# 0084_-_MCU.net
KiCad netlist of a schematic drawn in Altium Designer
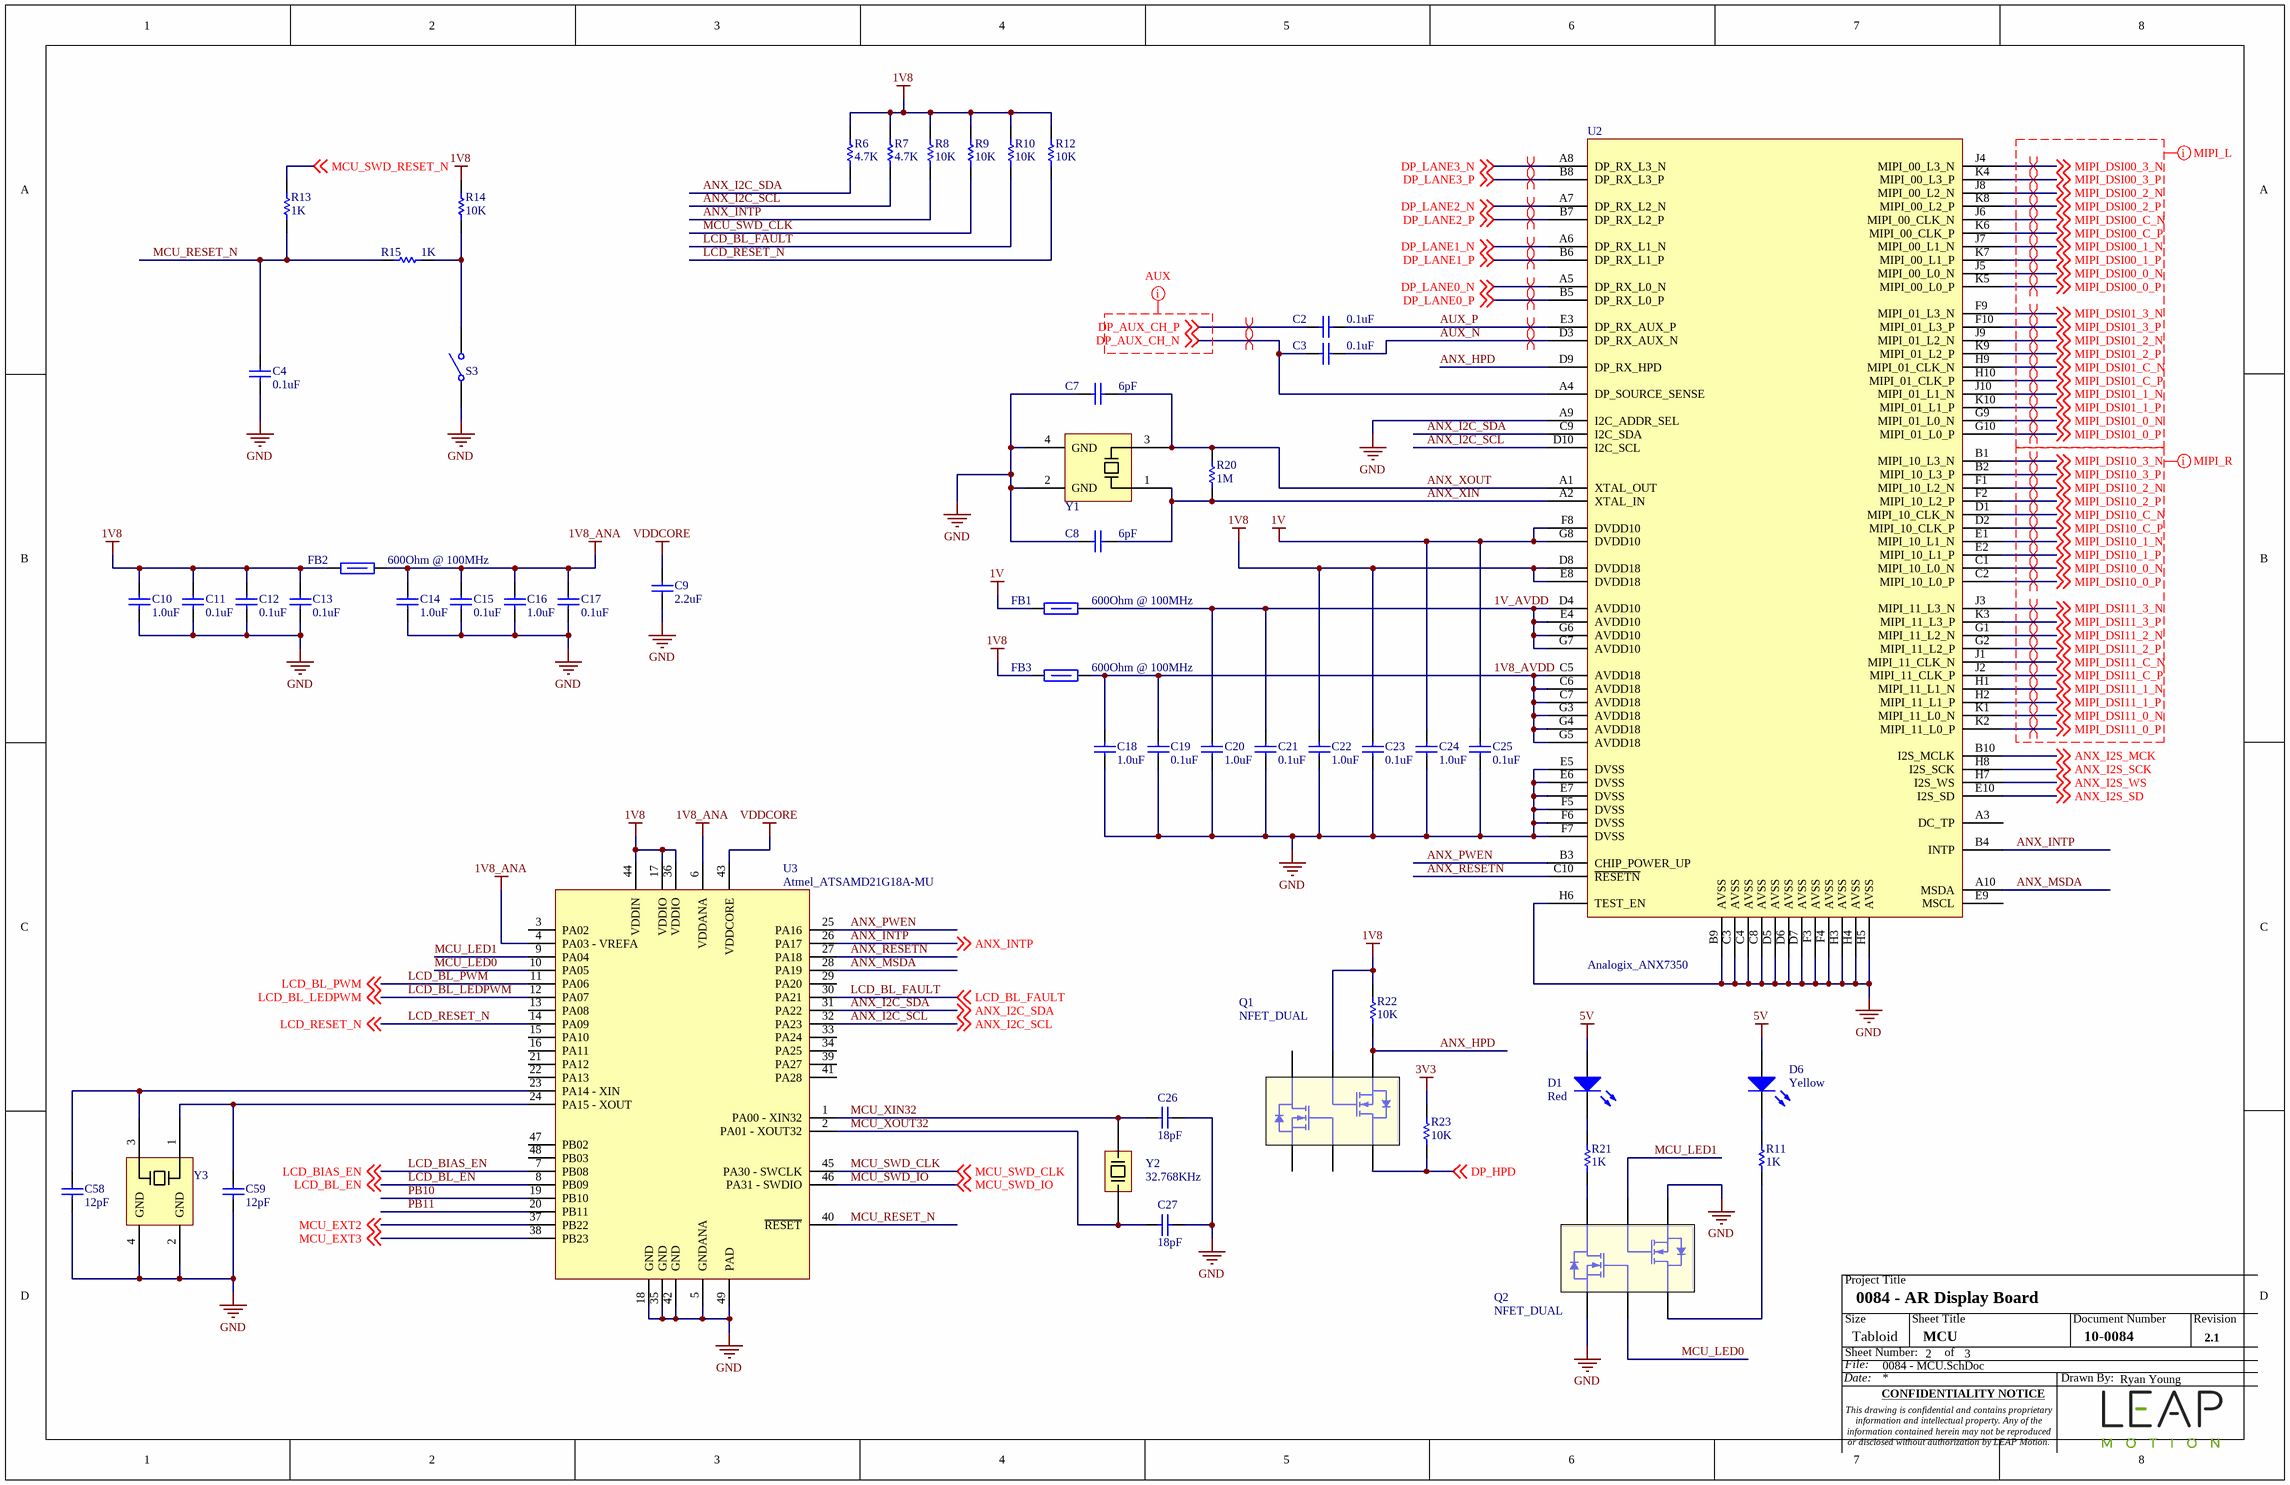
[diagram p0: 0084 - MCU.SchDoc]

(export (version "E")
  (design (tool "Eeschema 10.0.6"))
  (components
    (comp (ref "C2")
      (value "0.1uF")
      (footprint "CAPC0201(0603)33_N")
      (description "Capacitor, 0.1uF, 10V, 10%, 0201, Ceramic, X5R")
      (fields
        (field (name "MANUFACTURER") "Murata")
        (field (name "TOLERANCE") "10%")
        (field (name "AUTHOR") "AA")
      )
      (libsource (lib "LEAPdb") (part "CAP"))
    )
    (comp (ref "C3")
      (value "0.1uF")
      (footprint "CAPC0201(0603)33_N")
      (description "Capacitor, 0.1uF, 10V, 10%, 0201, Ceramic, X5R")
      (fields
        (field (name "MANUFACTURER") "Murata")
        (field (name "TOLERANCE") "10%")
        (field (name "AUTHOR") "AA")
      )
      (libsource (lib "LEAPdb") (part "CAP"))
    )
    (comp (ref "C4")
      (value "0.1uF")
      (footprint "CAPC0201(0603)33_N")
      (description "Capacitor, 0.1uF, 10V, 10%, 0201, Ceramic, X5R")
      (fields
        (field (name "MANUFACTURER") "Murata")
        (field (name "TOLERANCE") "10%")
        (field (name "AUTHOR") "AA")
      )
      (libsource (lib "LEAPdb") (part "CAP"))
    )
    (comp (ref "C7")
      (value "6pF")
      (footprint "CAPC0201(0603)33_N")
      (description "Capacitor, 6pF, 50V, 0.1pF, 0201, Ceramic, C0G(NP0)")
      (fields
        (field (name "MANUFACTURER") "Murata")
        (field (name "TOLERANCE") "0.1pF")
        (field (name "AUTHOR") "RY")
      )
      (libsource (lib "LEAPdb") (part "CAP"))
    )
    (comp (ref "C8")
      (value "6pF")
      (footprint "CAPC0201(0603)33_N")
      (description "Capacitor, 6pF, 50V, 0.1pF, 0201, Ceramic, C0G(NP0)")
      (fields
        (field (name "MANUFACTURER") "Murata")
        (field (name "TOLERANCE") "0.1pF")
        (field (name "AUTHOR") "RY")
      )
      (libsource (lib "LEAPdb") (part "CAP"))
    )
    (comp (ref "C9")
      (value "2.2uF")
      (footprint "CAPC0402(1005)60_N")
      (description "Capacitor, 2.2uF, 6.3V, 20%, 0402, Ceramic, X5R")
      (fields
        (field (name "MANUFACTURER") "TDK")
        (field (name "TOLERANCE") "20%")
        (field (name "AUTHOR") "NR")
      )
      (libsource (lib "LEAPdb") (part "CAP"))
    )
    (comp (ref "C10")
      (value "1.0uF")
      (footprint "CAPC0402(1005)60_N")
      (description "Capacitor, 1.0uF, 10V, 10%, 0402, Ceramic, X5R")
      (fields
        (field (name "MANUFACTURER") "TDK")
        (field (name "TOLERANCE") "10%")
        (field (name "AUTHOR") "NR")
      )
      (libsource (lib "LEAPdb") (part "CAP"))
    )
    (comp (ref "C11")
      (value "0.1uF")
      (footprint "CAPC0201(0603)33_N")
      (description "Capacitor, 0.1uF, 10V, 10%, 0201, Ceramic, X5R")
      (fields
        (field (name "MANUFACTURER") "Murata")
        (field (name "TOLERANCE") "10%")
        (field (name "AUTHOR") "AA")
      )
      (libsource (lib "LEAPdb") (part "CAP"))
    )
    (comp (ref "C12")
      (value "0.1uF")
      (footprint "CAPC0201(0603)33_N")
      (description "Capacitor, 0.1uF, 10V, 10%, 0201, Ceramic, X5R")
      (fields
        (field (name "MANUFACTURER") "Murata")
        (field (name "TOLERANCE") "10%")
        (field (name "AUTHOR") "AA")
      )
      (libsource (lib "LEAPdb") (part "CAP"))
    )
    (comp (ref "C13")
      (value "0.1uF")
      (footprint "CAPC0201(0603)33_N")
      (description "Capacitor, 0.1uF, 10V, 10%, 0201, Ceramic, X5R")
      (fields
        (field (name "MANUFACTURER") "Murata")
        (field (name "TOLERANCE") "10%")
        (field (name "AUTHOR") "AA")
      )
      (libsource (lib "LEAPdb") (part "CAP"))
    )
    (comp (ref "C14")
      (value "1.0uF")
      (footprint "CAPC0402(1005)60_N")
      (description "Capacitor, 1.0uF, 10V, 10%, 0402, Ceramic, X5R")
      (fields
        (field (name "MANUFACTURER") "TDK")
        (field (name "TOLERANCE") "10%")
        (field (name "AUTHOR") "NR")
      )
      (libsource (lib "LEAPdb") (part "CAP"))
    )
    (comp (ref "C15")
      (value "0.1uF")
      (footprint "CAPC0201(0603)33_N")
      (description "Capacitor, 0.1uF, 10V, 10%, 0201, Ceramic, X5R")
      (fields
        (field (name "MANUFACTURER") "Murata")
        (field (name "TOLERANCE") "10%")
        (field (name "AUTHOR") "AA")
      )
      (libsource (lib "LEAPdb") (part "CAP"))
    )
    (comp (ref "C16")
      (value "1.0uF")
      (footprint "CAPC0402(1005)60_N")
      (description "Capacitor, 1.0uF, 10V, 10%, 0402, Ceramic, X5R")
      (fields
        (field (name "MANUFACTURER") "TDK")
        (field (name "TOLERANCE") "10%")
        (field (name "AUTHOR") "NR")
      )
      (libsource (lib "LEAPdb") (part "CAP"))
    )
    (comp (ref "C17")
      (value "0.1uF")
      (footprint "CAPC0201(0603)33_N")
      (description "Capacitor, 0.1uF, 10V, 10%, 0201, Ceramic, X5R")
      (fields
        (field (name "MANUFACTURER") "Murata")
        (field (name "TOLERANCE") "10%")
        (field (name "AUTHOR") "AA")
      )
      (libsource (lib "LEAPdb") (part "CAP"))
    )
    (comp (ref "C18")
      (value "1.0uF")
      (footprint "CAPC0402(1005)60_L")
      (description "Capacitor, 1.0uF, 10V, 10%, 0402, Ceramic, X5R")
      (fields
        (field (name "MANUFACTURER") "TDK")
        (field (name "TOLERANCE") "10%")
        (field (name "AUTHOR") "NR")
      )
      (libsource (lib "LEAPdb") (part "CAP"))
    )
    (comp (ref "C19")
      (value "0.1uF")
      (footprint "CAPC0201(0603)33_L")
      (description "Capacitor, 0.1uF, 10V, 10%, 0201, Ceramic, X5R")
      (fields
        (field (name "MANUFACTURER") "Murata")
        (field (name "TOLERANCE") "10%")
        (field (name "AUTHOR") "AA")
      )
      (libsource (lib "LEAPdb") (part "CAP"))
    )
    (comp (ref "C20")
      (value "1.0uF")
      (footprint "CAPC0402(1005)60_L")
      (description "Capacitor, 1.0uF, 10V, 10%, 0402, Ceramic, X5R")
      (fields
        (field (name "MANUFACTURER") "TDK")
        (field (name "TOLERANCE") "10%")
        (field (name "AUTHOR") "NR")
      )
      (libsource (lib "LEAPdb") (part "CAP"))
    )
    (comp (ref "C21")
      (value "0.1uF")
      (footprint "CAPC0201(0603)33_L")
      (description "Capacitor, 0.1uF, 10V, 10%, 0201, Ceramic, X5R")
      (fields
        (field (name "MANUFACTURER") "Murata")
        (field (name "TOLERANCE") "10%")
        (field (name "AUTHOR") "AA")
      )
      (libsource (lib "LEAPdb") (part "CAP"))
    )
    (comp (ref "C22")
      (value "1.0uF")
      (footprint "CAPC0402(1005)60_L")
      (description "Capacitor, 1.0uF, 10V, 10%, 0402, Ceramic, X5R")
      (fields
        (field (name "MANUFACTURER") "TDK")
        (field (name "TOLERANCE") "10%")
        (field (name "AUTHOR") "NR")
      )
      (libsource (lib "LEAPdb") (part "CAP"))
    )
    (comp (ref "C23")
      (value "0.1uF")
      (footprint "CAPC0201(0603)33_L")
      (description "Capacitor, 0.1uF, 10V, 10%, 0201, Ceramic, X5R")
      (fields
        (field (name "MANUFACTURER") "Murata")
        (field (name "TOLERANCE") "10%")
        (field (name "AUTHOR") "AA")
      )
      (libsource (lib "LEAPdb") (part "CAP"))
    )
    (comp (ref "C24")
      (value "1.0uF")
      (footprint "CAPC0402(1005)60_L")
      (description "Capacitor, 1.0uF, 10V, 10%, 0402, Ceramic, X5R")
      (fields
        (field (name "MANUFACTURER") "TDK")
        (field (name "TOLERANCE") "10%")
        (field (name "AUTHOR") "NR")
      )
      (libsource (lib "LEAPdb") (part "CAP"))
    )
    (comp (ref "C25")
      (value "0.1uF")
      (footprint "CAPC0201(0603)33_L")
      (description "Capacitor, 0.1uF, 10V, 10%, 0201, Ceramic, X5R")
      (fields
        (field (name "MANUFACTURER") "Murata")
        (field (name "TOLERANCE") "10%")
        (field (name "AUTHOR") "AA")
      )
      (libsource (lib "LEAPdb") (part "CAP"))
    )
    (comp (ref "C26")
      (value "18pF")
      (footprint "CAPC0201(0603)33_N")
      (description "Capacitor, 18pF, 50V, 2%, 0201, Ceramic, C0G(NP0)")
      (fields
        (field (name "MANUFACTURER") "Murata")
        (field (name "TOLERANCE") "2%")
        (field (name "AUTHOR") "RY")
      )
      (libsource (lib "LEAPdb") (part "CAP"))
    )
    (comp (ref "C27")
      (value "18pF")
      (footprint "CAPC0201(0603)33_N")
      (description "Capacitor, 18pF, 50V, 2%, 0201, Ceramic, C0G(NP0)")
      (fields
        (field (name "MANUFACTURER") "Murata")
        (field (name "TOLERANCE") "2%")
        (field (name "AUTHOR") "RY")
      )
      (libsource (lib "LEAPdb") (part "CAP"))
    )
    (comp (ref "C58")
      (value "12pF")
      (footprint "CAPC0201(0603)33_N")
      (description "Capacitor, 12pF, 50V, 2%, 0201, Ceramic, C0G(NP0)")
      (fields
        (field (name "MANUFACTURER") "Murata")
        (field (name "TOLERANCE") "2%")
        (field (name "AUTHOR") "RY")
      )
      (libsource (lib "LEAPdb") (part "CAP"))
    )
    (comp (ref "C59")
      (value "12pF")
      (footprint "CAPC0201(0603)33_N")
      (description "Capacitor, 12pF, 50V, 2%, 0201, Ceramic, C0G(NP0)")
      (fields
        (field (name "MANUFACTURER") "Murata")
        (field (name "TOLERANCE") "2%")
        (field (name "AUTHOR") "RY")
      )
      (libsource (lib "LEAPdb") (part "CAP"))
    )
    (comp (ref "D1")
      (value "~")
      (footprint "Dialight_598-8010-107F")
      (description "LED, 635nm, 140deg, , 20mA, , 1.6mm x 0.8mm, -30C - 85C")
      (fields
        (field (name "MANUFACTURER") "Dialight")
        (field (name "COLOR") "Red")
        (field (name "AUTHOR") "JDS")
      )
      (libsource (lib "LEAPdb") (part "LED"))
    )
    (comp (ref "D6")
      (value "~")
      (footprint "Dialight_598-8040-107F")
      (description "LED, 593nm, 140deg, , 20mA, , 1.6mm x 0.8mm, -30C - 85C")
      (fields
        (field (name "MANUFACTURER") "Dialight")
        (field (name "COLOR") "Yellow")
        (field (name "AUTHOR") "JDS")
      )
      (libsource (lib "LEAPdb") (part "LED"))
    )
    (comp (ref "FB1")
      (value "Ferrite Bead")
      (footprint "INDC1608X09N")
      (description "FERRITE CHIP BEAD 600 OHM SMD")
      (fields
        (field (name "MANUFACTURER") "TDK")
        (field (name "IMPEDANCE @ FREQ") "600Ohm @ 100MHz")
        (field (name "AUTHOR") "NR")
      )
      (libsource (lib "LEAPdb") (part "Ferrite Bead"))
    )
    (comp (ref "FB2")
      (value "Ferrite Bead")
      (footprint "INDC1608X09N")
      (description "FERRITE CHIP BEAD 600 OHM SMD")
      (fields
        (field (name "MANUFACTURER") "TDK")
        (field (name "IMPEDANCE @ FREQ") "600Ohm @ 100MHz")
        (field (name "AUTHOR") "NR")
      )
      (libsource (lib "LEAPdb") (part "Ferrite Bead"))
    )
    (comp (ref "FB3")
      (value "Ferrite Bead")
      (footprint "INDC1608X09N")
      (description "FERRITE CHIP BEAD 600 OHM SMD")
      (fields
        (field (name "MANUFACTURER") "TDK")
        (field (name "IMPEDANCE @ FREQ") "600Ohm @ 100MHz")
        (field (name "AUTHOR") "NR")
      )
      (libsource (lib "LEAPdb") (part "Ferrite Bead"))
    )
    (comp (ref "Q1")
      (value "NFET_DUAL")
      (footprint "SOT-563")
      (description "Transistor, NFET_DUAL, 2.2Ohm, 200mA, 120mW, 	SOT-563, -55C - 150C")
      (fields (field (name "MANUFACTURER") "Rohm Semiconductor") (field (name "AUTHOR") "RY"))
      (libsource (lib "LEAPdb") (part "NFET_DUAL"))
    )
    (comp (ref "Q2")
      (value "NFET_DUAL")
      (footprint "SOT-563")
      (description "Transistor, NFET_DUAL, 2.2Ohm, 200mA, 120mW, 	SOT-563, -55C - 150C")
      (fields (field (name "MANUFACTURER") "Rohm Semiconductor") (field (name "AUTHOR") "RY"))
      (libsource (lib "LEAPdb") (part "NFET_DUAL"))
    )
    (comp (ref "R6")
      (value "4.7K")
      (footprint "RESC0201(0603)_N")
      (description "Resistor, 4.7K, 1/20W, 1%, 0201")
      (fields
        (field (name "MANUFACTURER") "Panasonic Electronic Components")
        (field (name "TOLERANCE") "1%")
        (field (name "AUTHOR") "NR")
      )
      (libsource (lib "LEAPdb") (part "RES"))
    )
    (comp (ref "R7")
      (value "4.7K")
      (footprint "RESC0201(0603)_N")
      (description "Resistor, 4.7K, 1/20W, 1%, 0201")
      (fields
        (field (name "MANUFACTURER") "Panasonic Electronic Components")
        (field (name "TOLERANCE") "1%")
        (field (name "AUTHOR") "NR")
      )
      (libsource (lib "LEAPdb") (part "RES"))
    )
    (comp (ref "R8")
      (value "10K")
      (footprint "RESC0201(0603)_N")
      (description "Resistor, 10K, 1/20W, 5%, 0201")
      (fields
        (field (name "MANUFACTURER") "Panasonic Electronic Components")
        (field (name "TOLERANCE") "5%")
        (field (name "AUTHOR") "NR")
      )
      (libsource (lib "LEAPdb") (part "RES"))
    )
    (comp (ref "R9")
      (value "10K")
      (footprint "RESC0201(0603)_N")
      (description "Resistor, 10K, 1/20W, 5%, 0201")
      (fields
        (field (name "MANUFACTURER") "Panasonic Electronic Components")
        (field (name "TOLERANCE") "5%")
        (field (name "AUTHOR") "NR")
      )
      (libsource (lib "LEAPdb") (part "RES"))
    )
    (comp (ref "R10")
      (value "10K")
      (footprint "RESC0201(0603)_N")
      (description "Resistor, 10K, 1/20W, 5%, 0201")
      (fields
        (field (name "MANUFACTURER") "Panasonic Electronic Components")
        (field (name "TOLERANCE") "5%")
        (field (name "AUTHOR") "NR")
      )
      (libsource (lib "LEAPdb") (part "RES"))
    )
    (comp (ref "R11")
      (value "1K")
      (footprint "RESC0201(0603)_N")
      (description "Resistor, 1K, 1/20W, 5%, 0201")
      (fields
        (field (name "MANUFACTURER") "Panasonic Electronic Components")
        (field (name "TOLERANCE") "5%")
        (field (name "AUTHOR") "JDS")
      )
      (libsource (lib "LEAPdb") (part "RES"))
    )
    (comp (ref "R12")
      (value "10K")
      (footprint "RESC0201(0603)_N")
      (description "Resistor, 10K, 1/20W, 5%, 0201")
      (fields
        (field (name "MANUFACTURER") "Panasonic Electronic Components")
        (field (name "TOLERANCE") "5%")
        (field (name "AUTHOR") "NR")
      )
      (libsource (lib "LEAPdb") (part "RES"))
    )
    (comp (ref "R13")
      (value "1K")
      (footprint "RESC0201(0603)_N")
      (description "Resistor, 1K, 1/20W, 5%, 0201")
      (fields
        (field (name "MANUFACTURER") "Panasonic Electronic Components")
        (field (name "TOLERANCE") "5%")
        (field (name "AUTHOR") "JDS")
      )
      (libsource (lib "LEAPdb") (part "RES"))
    )
    (comp (ref "R14")
      (value "10K")
      (footprint "RESC0201(0603)_N")
      (description "Resistor, 10K, 1/20W, 5%, 0201")
      (fields
        (field (name "MANUFACTURER") "Panasonic Electronic Components")
        (field (name "TOLERANCE") "5%")
        (field (name "AUTHOR") "NR")
      )
      (libsource (lib "LEAPdb") (part "RES"))
    )
    (comp (ref "R15")
      (value "1K")
      (footprint "RESC0201(0603)_N")
      (description "Resistor, 1K, 1/20W, 5%, 0201")
      (fields
        (field (name "MANUFACTURER") "Panasonic Electronic Components")
        (field (name "TOLERANCE") "5%")
        (field (name "AUTHOR") "JDS")
      )
      (libsource (lib "LEAPdb") (part "RES"))
    )
    (comp (ref "R20")
      (value "1M")
      (footprint "RESC0201(0603)_N")
      (description "Resistor, 1M, 1/20W, 1%, 0201")
      (fields
        (field (name "MANUFACTURER") "Panasonic Electronic Components")
        (field (name "TOLERANCE") "1%")
        (field (name "AUTHOR") "RY")
      )
      (libsource (lib "LEAPdb") (part "RES"))
    )
    (comp (ref "R21")
      (value "1K")
      (footprint "RESC0201(0603)_N")
      (description "Resistor, 1K, 1/20W, 5%, 0201")
      (fields
        (field (name "MANUFACTURER") "Panasonic Electronic Components")
        (field (name "TOLERANCE") "5%")
        (field (name "AUTHOR") "JDS")
      )
      (libsource (lib "LEAPdb") (part "RES"))
    )
    (comp (ref "R22")
      (value "10K")
      (footprint "RESC0201(0603)_N")
      (description "Resistor, 10K, 1/20W, 5%, 0201")
      (fields
        (field (name "MANUFACTURER") "Panasonic Electronic Components")
        (field (name "TOLERANCE") "5%")
        (field (name "AUTHOR") "NR")
      )
      (libsource (lib "LEAPdb") (part "RES"))
    )
    (comp (ref "R23")
      (value "10K")
      (footprint "RESC0201(0603)_N")
      (description "Resistor, 10K, 1/20W, 5%, 0201")
      (fields
        (field (name "MANUFACTURER") "Panasonic Electronic Components")
        (field (name "TOLERANCE") "5%")
        (field (name "AUTHOR") "NR")
      )
      (libsource (lib "LEAPdb") (part "RES"))
    )
    (comp (ref "S3")
      (value "SW-SPST")
      (footprint "ALPS_SKRPABE010")
      (description "Switch, SPST-NO, Button, 4.6mm x 3.2mm")
      (fields (field (name "MANUFACTURER") "ALPS") (field (name "AUTHOR") "JDS"))
      (libsource (lib "LEAPdb") (part "SW-SPST"))
    )
    (comp (ref "U2")
      (value "Analogix_ANX7350")
      (footprint "Analogix_ANX7350")
      (description "DisplayPort 1.4-to-Dual MIPI Output Converter")
      (fields (field (name "MANUFACTURER") "Analogix") (field (name "AUTHOR") "RY"))
      (libsource (lib "LEAPdb") (part "Analogix_ANX7350"))
    )
    (comp (ref "U3")
      (value "Atmel_ATSAMD21G18A-MU")
      (footprint "Atmel_ATSAMD21G18A-MU")
      (description "IC MCU 32BIT 256KB FLASH 48QFN")
      (fields (field (name "MANUFACTURER") "Atmel") (field (name "AUTHOR") "RY"))
      (libsource (lib "LEAPdb") (part "Atmel_ATSAMD21G18A-MU"))
    )
    (comp (ref "Y1")
      (value "Crystal")
      (footprint "Abracon_ABM11")
      (description "Crystal, 24MHz, 6pF, 4-SMD (2x1.6)")
      (fields
        (field (name "MANUFACTURER") "Abracon")
        (field (name "TOLERANCE") "20ppm")
        (field (name "AUTHOR") "AA")
      )
      (libsource (lib "LEAPdb") (part "Crystal"))
    )
    (comp (ref "Y2")
      (value "Crystal_2pin")
      (footprint "Abracon_ABS07")
      (description "Crystal, 32.768KHz, 12.5pF, 2-SMD(3.2x1.5)")
      (fields
        (field (name "MANUFACTURER") "Abracon")
        (field (name "FREQUENCY") "32.768KHz")
        (field (name "TOLERANCE") "20 ppm")
        (field (name "AUTHOR") "JDS")
      )
      (libsource (lib "LEAPdb") (part "Crystal_2pin"))
    )
    (comp (ref "Y3")
      (value "Crystal")
      (footprint "Abracon_ABM11")
      (description "Crystal, 16MHz, 10pF, 4-SMD (2x1.6)")
      (fields
        (field (name "MANUFACTURER") "Abracon")
        (field (name "TOLERANCE") "20ppm")
        (field (name "AUTHOR") "JDS")
      )
      (libsource (lib "") (part "Crystal_1"))
    )
  )
  (nets
    (net (code "1") (name "/1V8_AVDD") (class "Default")
      (node (ref "C18") (pin "2") (pinfunction "2_2") (pintype "passive"))
      (node (ref "C19") (pin "2") (pinfunction "2_2") (pintype "passive"))
      (node (ref "FB3") (pin "2") (pinfunction "2_2") (pintype "passive"))
      (node (ref "U2") (pin "C5") (pinfunction "AVDD18_C5") (pintype "passive"))
      (node (ref "U2") (pin "C6") (pinfunction "AVDD18_C6") (pintype "passive"))
      (node (ref "U2") (pin "C7") (pinfunction "AVDD18_C7") (pintype "passive"))
      (node (ref "U2") (pin "G3") (pinfunction "AVDD18_G3") (pintype "passive"))
      (node (ref "U2") (pin "G4") (pinfunction "AVDD18_G4") (pintype "passive"))
      (node (ref "U2") (pin "G5") (pinfunction "AVDD18_G5") (pintype "passive"))
    )
    (net (code "2") (name "/1V_AVDD") (class "Default")
      (node (ref "C20") (pin "2") (pinfunction "2_2") (pintype "passive"))
      (node (ref "C21") (pin "2") (pinfunction "2_2") (pintype "passive"))
      (node (ref "FB1") (pin "2") (pinfunction "2_2") (pintype "passive"))
      (node (ref "U2") (pin "D4") (pinfunction "AVDD10_D4") (pintype "passive"))
      (node (ref "U2") (pin "E4") (pinfunction "AVDD10_E4") (pintype "passive"))
      (node (ref "U2") (pin "G6") (pinfunction "AVDD10_G6") (pintype "passive"))
      (node (ref "U2") (pin "G7") (pinfunction "AVDD10_G7") (pintype "passive"))
    )
    (net (code "3") (name "/ANX_HPD") (class "Default")
      (node (ref "Q1") (pin "4") (pinfunction "S2_4") (pintype "passive"))
      (node (ref "R22") (pin "1") (pinfunction "1_1") (pintype "passive"))
      (node (ref "U2") (pin "D9") (pinfunction "DP_RX_HPD_D9") (pintype "passive"))
    )
    (net (code "4") (name "/ANX_MSDA") (class "Default")
      (node (ref "U2") (pin "A10") (pinfunction "MSDA_A10") (pintype "passive"))
      (node (ref "U3") (pin "28") (pinfunction "PA19_28") (pintype "passive"))
    )
    (net (code "5") (name "/ANX_PWEN") (class "Default")
      (node (ref "U2") (pin "B3") (pinfunction "CHIP_POWER_UP_B3") (pintype "passive"))
      (node (ref "U3") (pin "25") (pinfunction "PA16_25") (pintype "passive"))
    )
    (net (code "6") (name "/ANX_RESETN") (class "Default")
      (node (ref "U2") (pin "C10") (pinfunction "~{RESETN}_C10") (pintype "passive"))
      (node (ref "U3") (pin "27") (pinfunction "PA18_27") (pintype "passive"))
    )
    (net (code "7") (name "/ANX_XIN") (class "Default")
      (node (ref "C8") (pin "1") (pinfunction "1_1") (pintype "passive"))
      (node (ref "R20") (pin "1") (pinfunction "1_1") (pintype "passive"))
      (node (ref "U2") (pin "A2") (pinfunction "XTAL_IN_A2") (pintype "passive"))
      (node (ref "Y1") (pin "1") (pinfunction "XTAL1_1") (pintype "passive"))
    )
    (net (code "8") (name "/ANX_XOUT") (class "Default")
      (node (ref "C7") (pin "1") (pinfunction "1_1") (pintype "passive"))
      (node (ref "R20") (pin "2") (pinfunction "2_2") (pintype "passive"))
      (node (ref "U2") (pin "A1") (pinfunction "XTAL_OUT_A1") (pintype "passive"))
      (node (ref "Y1") (pin "3") (pinfunction "XTAL2_3") (pintype "passive"))
    )
    (net (code "9") (name "/AUX_N") (class "Default")
      (node (ref "C3") (pin "1") (pinfunction "1_1") (pintype "passive"))
      (node (ref "U2") (pin "D3") (pinfunction "DP_RX_AUX_N_D3") (pintype "passive"))
    )
    (net (code "10") (name "/AUX_P") (class "Default")
      (node (ref "C2") (pin "1") (pinfunction "1_1") (pintype "passive"))
      (node (ref "U2") (pin "E3") (pinfunction "DP_RX_AUX_P_E3") (pintype "passive"))
    )
    (net (code "11") (name "/MCU_LED0") (class "Default")
      (node (ref "Q2") (pin "2") (pinfunction "G1_2") (pintype "passive"))
      (node (ref "U3") (pin "10") (pinfunction "PA05_10") (pintype "passive"))
    )
    (net (code "12") (name "/MCU_LED1") (class "Default")
      (node (ref "Q2") (pin "5") (pinfunction "G2_5") (pintype "passive"))
      (node (ref "U3") (pin "9") (pinfunction "PA04_9") (pintype "passive"))
    )
    (net (code "13") (name "/MCU_RESET_N") (class "Default")
      (node (ref "C4") (pin "2") (pinfunction "2_2") (pintype "passive"))
      (node (ref "R13") (pin "2") (pinfunction "2_2") (pintype "passive"))
      (node (ref "R15") (pin "2") (pinfunction "2_2") (pintype "passive"))
      (node (ref "U3") (pin "40") (pinfunction "~{RESET}_40") (pintype "passive"))
    )
    (net (code "14") (name "/MCU_XIN32") (class "Default")
      (node (ref "C26") (pin "1") (pinfunction "1_1") (pintype "passive"))
      (node (ref "U3") (pin "1") (pinfunction "PA00_-_XIN32_1") (pintype "passive"))
      (node (ref "Y2") (pin "1") (pinfunction "XTAL2_1") (pintype "passive"))
    )
    (net (code "15") (name "/MCU_XOUT32") (class "Default")
      (node (ref "C27") (pin "1") (pinfunction "1_1") (pintype "passive"))
      (node (ref "U3") (pin "2") (pinfunction "PA01_-_XOUT32_2") (pintype "passive"))
      (node (ref "Y2") (pin "0") (pinfunction "XTAL1_0") (pintype "passive"))
    )
    (net (code "16") (name "/PB10") (class "Default")
      (node (ref "U3") (pin "19") (pinfunction "PB10_19") (pintype "passive"))
    )
    (net (code "17") (name "/PB11") (class "Default")
      (node (ref "U3") (pin "20") (pinfunction "PB11_20") (pintype "passive"))
    )
    (net (code "18") (name "1V") (class "Default")
      (node (ref "C24") (pin "2") (pinfunction "2_2") (pintype "passive"))
      (node (ref "C25") (pin "2") (pinfunction "2_2") (pintype "passive"))
      (node (ref "FB1") (pin "1") (pinfunction "1_1") (pintype "passive"))
      (node (ref "U2") (pin "F8") (pinfunction "DVDD10_F8") (pintype "passive"))
      (node (ref "U2") (pin "G8") (pinfunction "DVDD10_G8") (pintype "passive"))
    )
    (net (code "19") (name "1V8") (class "Default")
      (node (ref "C10") (pin "2") (pinfunction "2_2") (pintype "passive"))
      (node (ref "C11") (pin "2") (pinfunction "2_2") (pintype "passive"))
      (node (ref "C12") (pin "2") (pinfunction "2_2") (pintype "passive"))
      (node (ref "C13") (pin "2") (pinfunction "2_2") (pintype "passive"))
      (node (ref "C22") (pin "2") (pinfunction "2_2") (pintype "passive"))
      (node (ref "C23") (pin "2") (pinfunction "2_2") (pintype "passive"))
      (node (ref "FB2") (pin "1") (pinfunction "1_1") (pintype "passive"))
      (node (ref "FB3") (pin "1") (pinfunction "1_1") (pintype "passive"))
      (node (ref "Q1") (pin "5") (pinfunction "G2_5") (pintype "passive"))
      (node (ref "R10") (pin "2") (pinfunction "2_2") (pintype "passive"))
      (node (ref "R12") (pin "2") (pinfunction "2_2") (pintype "passive"))
      (node (ref "R14") (pin "2") (pinfunction "2_2") (pintype "passive"))
      (node (ref "R22") (pin "2") (pinfunction "2_2") (pintype "passive"))
      (node (ref "R6") (pin "2") (pinfunction "2_2") (pintype "passive"))
      (node (ref "R7") (pin "2") (pinfunction "2_2") (pintype "passive"))
      (node (ref "R8") (pin "2") (pinfunction "2_2") (pintype "passive"))
      (node (ref "R9") (pin "2") (pinfunction "2_2") (pintype "passive"))
      (node (ref "U2") (pin "D8") (pinfunction "DVDD18_D8") (pintype "passive"))
      (node (ref "U2") (pin "E8") (pinfunction "DVDD18_E8") (pintype "passive"))
      (node (ref "U3") (pin "17") (pinfunction "VDDIO_17") (pintype "passive"))
      (node (ref "U3") (pin "36") (pinfunction "VDDIO_36") (pintype "passive"))
      (node (ref "U3") (pin "44") (pinfunction "VDDIN_44") (pintype "passive"))
    )
    (net (code "20") (name "1V8_ANA") (class "Default")
      (node (ref "C14") (pin "2") (pinfunction "2_2") (pintype "passive"))
      (node (ref "C15") (pin "2") (pinfunction "2_2") (pintype "passive"))
      (node (ref "C16") (pin "2") (pinfunction "2_2") (pintype "passive"))
      (node (ref "C17") (pin "2") (pinfunction "2_2") (pintype "passive"))
      (node (ref "FB2") (pin "2") (pinfunction "2_2") (pintype "passive"))
      (node (ref "U3") (pin "4") (pinfunction "PA03_-_VREFA_4") (pintype "passive"))
      (node (ref "U3") (pin "6") (pinfunction "VDDANA_6") (pintype "passive"))
    )
    (net (code "21") (name "3V3") (class "Default")
      (node (ref "R23") (pin "1") (pinfunction "1_1") (pintype "passive"))
    )
    (net (code "22") (name "5V") (class "Default")
      (node (ref "D1") (pin "A") (pinfunction "A_A") (pintype "passive"))
      (node (ref "D6") (pin "A") (pinfunction "A_A") (pintype "passive"))
    )
    (net (code "23") (name "ANX_I2C_SCL") (class "Default")
      (node (ref "R7") (pin "1") (pinfunction "1_1") (pintype "passive"))
      (node (ref "U2") (pin "D10") (pinfunction "I2C_SCL_D10") (pintype "passive"))
      (node (ref "U3") (pin "32") (pinfunction "PA23_32") (pintype "passive"))
    )
    (net (code "24") (name "ANX_I2C_SDA") (class "Default")
      (node (ref "R6") (pin "1") (pinfunction "1_1") (pintype "passive"))
      (node (ref "U2") (pin "C9") (pinfunction "I2C_SDA_C9") (pintype "passive"))
      (node (ref "U3") (pin "31") (pinfunction "PA22_31") (pintype "passive"))
    )
    (net (code "25") (name "ANX_I2S_MCK") (class "Default")
      (node (ref "U2") (pin "B10") (pinfunction "I2S_MCLK_B10") (pintype "passive"))
    )
    (net (code "26") (name "ANX_I2S_SCK") (class "Default")
      (node (ref "U2") (pin "H8") (pinfunction "I2S_SCK_H8") (pintype "passive"))
    )
    (net (code "27") (name "ANX_I2S_SD") (class "Default")
      (node (ref "U2") (pin "E10") (pinfunction "I2S_SD_E10") (pintype "passive"))
    )
    (net (code "28") (name "ANX_I2S_WS") (class "Default")
      (node (ref "U2") (pin "H7") (pinfunction "I2S_WS_H7") (pintype "passive"))
    )
    (net (code "29") (name "ANX_INTP") (class "Default")
      (node (ref "R8") (pin "1") (pinfunction "1_1") (pintype "passive"))
      (node (ref "U2") (pin "B4") (pinfunction "INTP_B4") (pintype "passive"))
      (node (ref "U3") (pin "26") (pinfunction "PA17_26") (pintype "passive"))
    )
    (net (code "30") (name "DP_AUX_CH_N") (class "Default")
      (node (ref "C3") (pin "2") (pinfunction "2_2") (pintype "passive"))
      (node (ref "U2") (pin "A4") (pinfunction "DP_SOURCE_SENSE_A4") (pintype "passive"))
    )
    (net (code "31") (name "DP_AUX_CH_P") (class "Default")
      (node (ref "C2") (pin "2") (pinfunction "2_2") (pintype "passive"))
    )
    (net (code "32") (name "DP_HPD") (class "Default")
      (node (ref "Q1") (pin "3") (pinfunction "D2_3") (pintype "passive"))
      (node (ref "R23") (pin "2") (pinfunction "2_2") (pintype "passive"))
    )
    (net (code "33") (name "DP_LANE0_N") (class "Default")
      (node (ref "U2") (pin "A5") (pinfunction "DP_RX_L0_N_A5") (pintype "passive"))
    )
    (net (code "34") (name "DP_LANE0_P") (class "Default")
      (node (ref "U2") (pin "B5") (pinfunction "DP_RX_L0_P_B5") (pintype "passive"))
    )
    (net (code "35") (name "DP_LANE1_N") (class "Default")
      (node (ref "U2") (pin "A6") (pinfunction "DP_RX_L1_N_A6") (pintype "passive"))
    )
    (net (code "36") (name "DP_LANE1_P") (class "Default")
      (node (ref "U2") (pin "B6") (pinfunction "DP_RX_L1_P_B6") (pintype "passive"))
    )
    (net (code "37") (name "DP_LANE2_N") (class "Default")
      (node (ref "U2") (pin "A7") (pinfunction "DP_RX_L2_N_A7") (pintype "passive"))
    )
    (net (code "38") (name "DP_LANE2_P") (class "Default")
      (node (ref "U2") (pin "B7") (pinfunction "DP_RX_L2_P_B7") (pintype "passive"))
    )
    (net (code "39") (name "DP_LANE3_N") (class "Default")
      (node (ref "U2") (pin "A8") (pinfunction "DP_RX_L3_N_A8") (pintype "passive"))
    )
    (net (code "40") (name "DP_LANE3_P") (class "Default")
      (node (ref "U2") (pin "B8") (pinfunction "DP_RX_L3_P_B8") (pintype "passive"))
    )
    (net (code "41") (name "GND") (class "Default")
      (node (ref "C10") (pin "1") (pinfunction "1_1") (pintype "passive"))
      (node (ref "C11") (pin "1") (pinfunction "1_1") (pintype "passive"))
      (node (ref "C12") (pin "1") (pinfunction "1_1") (pintype "passive"))
      (node (ref "C13") (pin "1") (pinfunction "1_1") (pintype "passive"))
      (node (ref "C14") (pin "1") (pinfunction "1_1") (pintype "passive"))
      (node (ref "C15") (pin "1") (pinfunction "1_1") (pintype "passive"))
      (node (ref "C16") (pin "1") (pinfunction "1_1") (pintype "passive"))
      (node (ref "C17") (pin "1") (pinfunction "1_1") (pintype "passive"))
      (node (ref "C18") (pin "1") (pinfunction "1_1") (pintype "passive"))
      (node (ref "C19") (pin "1") (pinfunction "1_1") (pintype "passive"))
      (node (ref "C20") (pin "1") (pinfunction "1_1") (pintype "passive"))
      (node (ref "C21") (pin "1") (pinfunction "1_1") (pintype "passive"))
      (node (ref "C22") (pin "1") (pinfunction "1_1") (pintype "passive"))
      (node (ref "C23") (pin "1") (pinfunction "1_1") (pintype "passive"))
      (node (ref "C24") (pin "1") (pinfunction "1_1") (pintype "passive"))
      (node (ref "C25") (pin "1") (pinfunction "1_1") (pintype "passive"))
      (node (ref "C26") (pin "2") (pinfunction "2_2") (pintype "passive"))
      (node (ref "C27") (pin "2") (pinfunction "2_2") (pintype "passive"))
      (node (ref "C4") (pin "1") (pinfunction "1_1") (pintype "passive"))
      (node (ref "C58") (pin "2") (pinfunction "2_2") (pintype "passive"))
      (node (ref "C59") (pin "2") (pinfunction "2_2") (pintype "passive"))
      (node (ref "C7") (pin "2") (pinfunction "2_2") (pintype "passive"))
      (node (ref "C8") (pin "2") (pinfunction "2_2") (pintype "passive"))
      (node (ref "C9") (pin "2") (pinfunction "2_2") (pintype "passive"))
      (node (ref "Q2") (pin "1") (pinfunction "S1_1") (pintype "passive"))
      (node (ref "Q2") (pin "4") (pinfunction "S2_4") (pintype "passive"))
      (node (ref "S3") (pin "1") (pinfunction "COMMON_1") (pintype "passive"))
      (node (ref "U2") (pin "A9") (pinfunction "I2C_ADDR_SEL_A9") (pintype "passive"))
      (node (ref "U2") (pin "B9") (pinfunction "AVSS_B9") (pintype "passive"))
      (node (ref "U2") (pin "C3") (pinfunction "AVSS_C3") (pintype "passive"))
      (node (ref "U2") (pin "C4") (pinfunction "AVSS_C4") (pintype "passive"))
      (node (ref "U2") (pin "C8") (pinfunction "AVSS_C8") (pintype "passive"))
      (node (ref "U2") (pin "D5") (pinfunction "AVSS_D5") (pintype "passive"))
      (node (ref "U2") (pin "D6") (pinfunction "AVSS_D6") (pintype "passive"))
      (node (ref "U2") (pin "D7") (pinfunction "AVSS_D7") (pintype "passive"))
      (node (ref "U2") (pin "E5") (pinfunction "DVSS_E5") (pintype "passive"))
      (node (ref "U2") (pin "E6") (pinfunction "DVSS_E6") (pintype "passive"))
      (node (ref "U2") (pin "E7") (pinfunction "DVSS_E7") (pintype "passive"))
      (node (ref "U2") (pin "F3") (pinfunction "AVSS_F3") (pintype "passive"))
      (node (ref "U2") (pin "F4") (pinfunction "AVSS_F4") (pintype "passive"))
      (node (ref "U2") (pin "F5") (pinfunction "DVSS_F5") (pintype "passive"))
      (node (ref "U2") (pin "F6") (pinfunction "DVSS_F6") (pintype "passive"))
      (node (ref "U2") (pin "F7") (pinfunction "DVSS_F7") (pintype "passive"))
      (node (ref "U2") (pin "H3") (pinfunction "AVSS_H3") (pintype "passive"))
      (node (ref "U2") (pin "H4") (pinfunction "AVSS_H4") (pintype "passive"))
      (node (ref "U2") (pin "H5") (pinfunction "AVSS_H5") (pintype "passive"))
      (node (ref "U2") (pin "H6") (pinfunction "TEST_EN_H6") (pintype "passive"))
      (node (ref "U3") (pin "18") (pinfunction "GND_18") (pintype "passive"))
      (node (ref "U3") (pin "35") (pinfunction "GND_35") (pintype "passive"))
      (node (ref "U3") (pin "42") (pinfunction "GND_42") (pintype "passive"))
      (node (ref "U3") (pin "49") (pinfunction "PAD_49") (pintype "passive"))
      (node (ref "U3") (pin "5") (pinfunction "GNDANA_5") (pintype "passive"))
      (node (ref "Y1") (pin "2") (pinfunction "GND_2") (pintype "passive"))
      (node (ref "Y1") (pin "4") (pinfunction "GND_4") (pintype "passive"))
      (node (ref "Y3") (pin "2") (pinfunction "GND_2") (pintype "passive"))
      (node (ref "Y3") (pin "4") (pinfunction "GND_4") (pintype "passive"))
    )
    (net (code "42") (name "LCD_BIAS_EN") (class "Default")
      (node (ref "U3") (pin "7") (pinfunction "PB08_7") (pintype "passive"))
    )
    (net (code "43") (name "LCD_BL_EN") (class "Default")
      (node (ref "U3") (pin "8") (pinfunction "PB09_8") (pintype "passive"))
    )
    (net (code "44") (name "LCD_BL_FAULT") (class "Default")
      (node (ref "R10") (pin "1") (pinfunction "1_1") (pintype "passive"))
      (node (ref "U3") (pin "30") (pinfunction "PA21_30") (pintype "passive"))
    )
    (net (code "45") (name "LCD_BL_LEDPWM") (class "Default")
      (node (ref "U3") (pin "12") (pinfunction "PA07_12") (pintype "passive"))
    )
    (net (code "46") (name "LCD_BL_PWM") (class "Default")
      (node (ref "U3") (pin "11") (pinfunction "PA06_11") (pintype "passive"))
    )
    (net (code "47") (name "LCD_RESET_N") (class "Default")
      (node (ref "R12") (pin "1") (pinfunction "1_1") (pintype "passive"))
      (node (ref "U3") (pin "14") (pinfunction "PA09_14") (pintype "passive"))
    )
    (net (code "48") (name "MCU_EXT2") (class "Default")
      (node (ref "U3") (pin "37") (pinfunction "PB22_37") (pintype "passive"))
    )
    (net (code "49") (name "MCU_EXT3") (class "Default")
      (node (ref "U3") (pin "38") (pinfunction "PB23_38") (pintype "passive"))
    )
    (net (code "50") (name "MCU_SWD_CLK") (class "Default")
      (node (ref "R9") (pin "1") (pinfunction "1_1") (pintype "passive"))
      (node (ref "U3") (pin "45") (pinfunction "PA30_-_SWCLK_45") (pintype "passive"))
    )
    (net (code "51") (name "MCU_SWD_IO") (class "Default")
      (node (ref "U3") (pin "46") (pinfunction "PA31_-_SWDIO_46") (pintype "passive"))
    )
    (net (code "52") (name "MCU_SWD_RESET_N") (class "Default")
      (node (ref "R13") (pin "1") (pinfunction "1_1") (pintype "passive"))
    )
    (net (code "53") (name "MIPI_DSI00_0_N") (class "Default")
      (node (ref "U2") (pin "J5") (pinfunction "MIPI_00_L0_N_J5") (pintype "passive"))
    )
    (net (code "54") (name "MIPI_DSI00_0_P") (class "Default")
      (node (ref "U2") (pin "K5") (pinfunction "MIPI_00_L0_P_K5") (pintype "passive"))
    )
    (net (code "55") (name "MIPI_DSI00_1_N") (class "Default")
      (node (ref "U2") (pin "J7") (pinfunction "MIPI_00_L1_N_J7") (pintype "passive"))
    )
    (net (code "56") (name "MIPI_DSI00_1_P") (class "Default")
      (node (ref "U2") (pin "K7") (pinfunction "MIPI_00_L1_P_K7") (pintype "passive"))
    )
    (net (code "57") (name "MIPI_DSI00_2_N") (class "Default")
      (node (ref "U2") (pin "J8") (pinfunction "MIPI_00_L2_N_J8") (pintype "passive"))
    )
    (net (code "58") (name "MIPI_DSI00_2_P") (class "Default")
      (node (ref "U2") (pin "K8") (pinfunction "MIPI_00_L2_P_K8") (pintype "passive"))
    )
    (net (code "59") (name "MIPI_DSI00_3_N") (class "Default")
      (node (ref "U2") (pin "J4") (pinfunction "MIPI_00_L3_N_J4") (pintype "passive"))
    )
    (net (code "60") (name "MIPI_DSI00_3_P") (class "Default")
      (node (ref "U2") (pin "K4") (pinfunction "MIPI_00_L3_P_K4") (pintype "passive"))
    )
    (net (code "61") (name "MIPI_DSI00_C_N") (class "Default")
      (node (ref "U2") (pin "J6") (pinfunction "MIPI_00_CLK_N_J6") (pintype "passive"))
    )
    (net (code "62") (name "MIPI_DSI00_C_P") (class "Default")
      (node (ref "U2") (pin "K6") (pinfunction "MIPI_00_CLK_P_K6") (pintype "passive"))
    )
    (net (code "63") (name "MIPI_DSI01_0_N") (class "Default")
      (node (ref "U2") (pin "G9") (pinfunction "MIPI_01_L0_N_G9") (pintype "passive"))
    )
    (net (code "64") (name "MIPI_DSI01_0_P") (class "Default")
      (node (ref "U2") (pin "G10") (pinfunction "MIPI_01_L0_P_G10") (pintype "passive"))
    )
    (net (code "65") (name "MIPI_DSI01_1_N") (class "Default")
      (node (ref "U2") (pin "J10") (pinfunction "MIPI_01_L1_N_J10") (pintype "passive"))
    )
    (net (code "66") (name "MIPI_DSI01_1_P") (class "Default")
      (node (ref "U2") (pin "K10") (pinfunction "MIPI_01_L1_P_K10") (pintype "passive"))
    )
    (net (code "67") (name "MIPI_DSI01_2_N") (class "Default")
      (node (ref "U2") (pin "J9") (pinfunction "MIPI_01_L2_N_J9") (pintype "passive"))
    )
    (net (code "68") (name "MIPI_DSI01_2_P") (class "Default")
      (node (ref "U2") (pin "K9") (pinfunction "MIPI_01_L2_P_K9") (pintype "passive"))
    )
    (net (code "69") (name "MIPI_DSI01_3_N") (class "Default")
      (node (ref "U2") (pin "F9") (pinfunction "MIPI_01_L3_N_F9") (pintype "passive"))
    )
    (net (code "70") (name "MIPI_DSI01_3_P") (class "Default")
      (node (ref "U2") (pin "F10") (pinfunction "MIPI_01_L3_P_F10") (pintype "passive"))
    )
    (net (code "71") (name "MIPI_DSI01_C_N") (class "Default")
      (node (ref "U2") (pin "H9") (pinfunction "MIPI_01_CLK_N_H9") (pintype "passive"))
    )
    (net (code "72") (name "MIPI_DSI01_C_P") (class "Default")
      (node (ref "U2") (pin "H10") (pinfunction "MIPI_01_CLK_P_H10") (pintype "passive"))
    )
    (net (code "73") (name "MIPI_DSI10_0_N") (class "Default")
      (node (ref "U2") (pin "C1") (pinfunction "MIPI_10_L0_N_C1") (pintype "passive"))
    )
    (net (code "74") (name "MIPI_DSI10_0_P") (class "Default")
      (node (ref "U2") (pin "C2") (pinfunction "MIPI_10_L0_P_C2") (pintype "passive"))
    )
    (net (code "75") (name "MIPI_DSI10_1_N") (class "Default")
      (node (ref "U2") (pin "E1") (pinfunction "MIPI_10_L1_N_E1") (pintype "passive"))
    )
    (net (code "76") (name "MIPI_DSI10_1_P") (class "Default")
      (node (ref "U2") (pin "E2") (pinfunction "MIPI_10_L1_P_E2") (pintype "passive"))
    )
    (net (code "77") (name "MIPI_DSI10_2_N") (class "Default")
      (node (ref "U2") (pin "F1") (pinfunction "MIPI_10_L2_N_F1") (pintype "passive"))
    )
    (net (code "78") (name "MIPI_DSI10_2_P") (class "Default")
      (node (ref "U2") (pin "F2") (pinfunction "MIPI_10_L2_P_F2") (pintype "passive"))
    )
    (net (code "79") (name "MIPI_DSI10_3_N") (class "Default")
      (node (ref "U2") (pin "B1") (pinfunction "MIPI_10_L3_N_B1") (pintype "passive"))
    )
    (net (code "80") (name "MIPI_DSI10_3_P") (class "Default")
      (node (ref "U2") (pin "B2") (pinfunction "MIPI_10_L3_P_B2") (pintype "passive"))
    )
    (net (code "81") (name "MIPI_DSI10_C_N") (class "Default")
      (node (ref "U2") (pin "D1") (pinfunction "MIPI_10_CLK_N_D1") (pintype "passive"))
    )
    (net (code "82") (name "MIPI_DSI10_C_P") (class "Default")
      (node (ref "U2") (pin "D2") (pinfunction "MIPI_10_CLK_P_D2") (pintype "passive"))
    )
    (net (code "83") (name "MIPI_DSI11_0_N") (class "Default")
      (node (ref "U2") (pin "K1") (pinfunction "MIPI_11_L0_N_K1") (pintype "passive"))
    )
    (net (code "84") (name "MIPI_DSI11_0_P") (class "Default")
      (node (ref "U2") (pin "K2") (pinfunction "MIPI_11_L0_P_K2") (pintype "passive"))
    )
    (net (code "85") (name "MIPI_DSI11_1_N") (class "Default")
      (node (ref "U2") (pin "H1") (pinfunction "MIPI_11_L1_N_H1") (pintype "passive"))
    )
    (net (code "86") (name "MIPI_DSI11_1_P") (class "Default")
      (node (ref "U2") (pin "H2") (pinfunction "MIPI_11_L1_P_H2") (pintype "passive"))
    )
    (net (code "87") (name "MIPI_DSI11_2_N") (class "Default")
      (node (ref "U2") (pin "G1") (pinfunction "MIPI_11_L2_N_G1") (pintype "passive"))
    )
    (net (code "88") (name "MIPI_DSI11_2_P") (class "Default")
      (node (ref "U2") (pin "G2") (pinfunction "MIPI_11_L2_P_G2") (pintype "passive"))
    )
    (net (code "89") (name "MIPI_DSI11_3_N") (class "Default")
      (node (ref "U2") (pin "J3") (pinfunction "MIPI_11_L3_N_J3") (pintype "passive"))
    )
    (net (code "90") (name "MIPI_DSI11_3_P") (class "Default")
      (node (ref "U2") (pin "K3") (pinfunction "MIPI_11_L3_P_K3") (pintype "passive"))
    )
    (net (code "91") (name "MIPI_DSI11_C_N") (class "Default")
      (node (ref "U2") (pin "J1") (pinfunction "MIPI_11_CLK_N_J1") (pintype "passive"))
    )
    (net (code "92") (name "MIPI_DSI11_C_P") (class "Default")
      (node (ref "U2") (pin "J2") (pinfunction "MIPI_11_CLK_P_J2") (pintype "passive"))
    )
    (net (code "93") (name "Net-(D1-PadK)") (class "Default")
      (node (ref "D1") (pin "K") (pinfunction "K_K") (pintype "passive"))
      (node (ref "R21") (pin "1") (pinfunction "1_1") (pintype "passive"))
    )
    (net (code "94") (name "Net-(D6-PadK)") (class "Default")
      (node (ref "D6") (pin "K") (pinfunction "K_K") (pintype "passive"))
      (node (ref "R11") (pin "1") (pinfunction "1_1") (pintype "passive"))
    )
    (net (code "95") (name "Net-(Q2-D1)") (class "Default")
      (node (ref "Q2") (pin "6") (pinfunction "D1_6") (pintype "passive"))
      (node (ref "R21") (pin "2") (pinfunction "2_2") (pintype "passive"))
    )
    (net (code "96") (name "Net-(Q2-D2)") (class "Default")
      (node (ref "Q2") (pin "3") (pinfunction "D2_3") (pintype "passive"))
      (node (ref "R11") (pin "2") (pinfunction "2_2") (pintype "passive"))
    )
    (net (code "97") (name "Net-(S3-NO)") (class "Default")
      (node (ref "R14") (pin "1") (pinfunction "1_1") (pintype "passive"))
      (node (ref "R15") (pin "1") (pinfunction "1_1") (pintype "passive"))
      (node (ref "S3") (pin "2") (pinfunction "NO_2") (pintype "passive"))
    )
    (net (code "98") (name "Net-(U3-PA14_-_XIN)") (class "Default")
      (node (ref "C58") (pin "1") (pinfunction "1_1") (pintype "passive"))
      (node (ref "U3") (pin "23") (pinfunction "PA14_-_XIN_23") (pintype "passive"))
      (node (ref "Y3") (pin "3") (pinfunction "XTAL2_3") (pintype "passive"))
    )
    (net (code "99") (name "Net-(U3-PA15_-_XOUT)") (class "Default")
      (node (ref "C59") (pin "1") (pinfunction "1_1") (pintype "passive"))
      (node (ref "U3") (pin "24") (pinfunction "PA15_-_XOUT_24") (pintype "passive"))
      (node (ref "Y3") (pin "1") (pinfunction "XTAL1_1") (pintype "passive"))
    )
    (net (code "100") (name "VDDCORE") (class "Default")
      (node (ref "C9") (pin "1") (pinfunction "1_1") (pintype "passive"))
      (node (ref "U3") (pin "43") (pinfunction "VDDCORE_43") (pintype "passive"))
    )
    (net (code "101") (name "unconnected-(Q1-D1-Pad6)") (class "Default")
      (node (ref "Q1") (pin "6") (pinfunction "D1_6") (pintype "passive"))
    )
    (net (code "102") (name "unconnected-(Q1-G1-Pad2)") (class "Default")
      (node (ref "Q1") (pin "2") (pinfunction "G1_2") (pintype "passive"))
    )
    (net (code "103") (name "unconnected-(Q1-S1-Pad1)") (class "Default")
      (node (ref "Q1") (pin "1") (pinfunction "S1_1") (pintype "passive"))
    )
    (net (code "104") (name "unconnected-(U2-DC_TP-PadA3)") (class "Default")
      (node (ref "U2") (pin "A3") (pinfunction "DC_TP_A3") (pintype "passive"))
    )
    (net (code "105") (name "unconnected-(U2-MSCL-PadE9)") (class "Default")
      (node (ref "U2") (pin "E9") (pinfunction "MSCL_E9") (pintype "passive"))
    )
    (net (code "106") (name "unconnected-(U3-PA02-Pad3)") (class "Default")
      (node (ref "U3") (pin "3") (pinfunction "PA02_3") (pintype "passive"))
    )
    (net (code "107") (name "unconnected-(U3-PA08-Pad13)") (class "Default")
      (node (ref "U3") (pin "13") (pinfunction "PA08_13") (pintype "passive"))
    )
    (net (code "108") (name "unconnected-(U3-PA10-Pad15)") (class "Default")
      (node (ref "U3") (pin "15") (pinfunction "PA10_15") (pintype "passive"))
    )
    (net (code "109") (name "unconnected-(U3-PA11-Pad16)") (class "Default")
      (node (ref "U3") (pin "16") (pinfunction "PA11_16") (pintype "passive"))
    )
    (net (code "110") (name "unconnected-(U3-PA12-Pad21)") (class "Default")
      (node (ref "U3") (pin "21") (pinfunction "PA12_21") (pintype "passive"))
    )
    (net (code "111") (name "unconnected-(U3-PA13-Pad22)") (class "Default")
      (node (ref "U3") (pin "22") (pinfunction "PA13_22") (pintype "passive"))
    )
    (net (code "112") (name "unconnected-(U3-PA20-Pad29)") (class "Default")
      (node (ref "U3") (pin "29") (pinfunction "PA20_29") (pintype "passive"))
    )
    (net (code "113") (name "unconnected-(U3-PA24-Pad33)") (class "Default")
      (node (ref "U3") (pin "33") (pinfunction "PA24_33") (pintype "passive"))
    )
    (net (code "114") (name "unconnected-(U3-PA25-Pad34)") (class "Default")
      (node (ref "U3") (pin "34") (pinfunction "PA25_34") (pintype "passive"))
    )
    (net (code "115") (name "unconnected-(U3-PA27-Pad39)") (class "Default")
      (node (ref "U3") (pin "39") (pinfunction "PA27_39") (pintype "passive"))
    )
    (net (code "116") (name "unconnected-(U3-PA28-Pad41)") (class "Default")
      (node (ref "U3") (pin "41") (pinfunction "PA28_41") (pintype "passive"))
    )
    (net (code "117") (name "unconnected-(U3-PB02-Pad47)") (class "Default")
      (node (ref "U3") (pin "47") (pinfunction "PB02_47") (pintype "passive"))
    )
    (net (code "118") (name "unconnected-(U3-PB03-Pad48)") (class "Default")
      (node (ref "U3") (pin "48") (pinfunction "PB03_48") (pintype "passive"))
    )
  )
)
